# SAU-G0-EX_microSD.net
KiCad netlist of a schematic drawn in Altium Designer
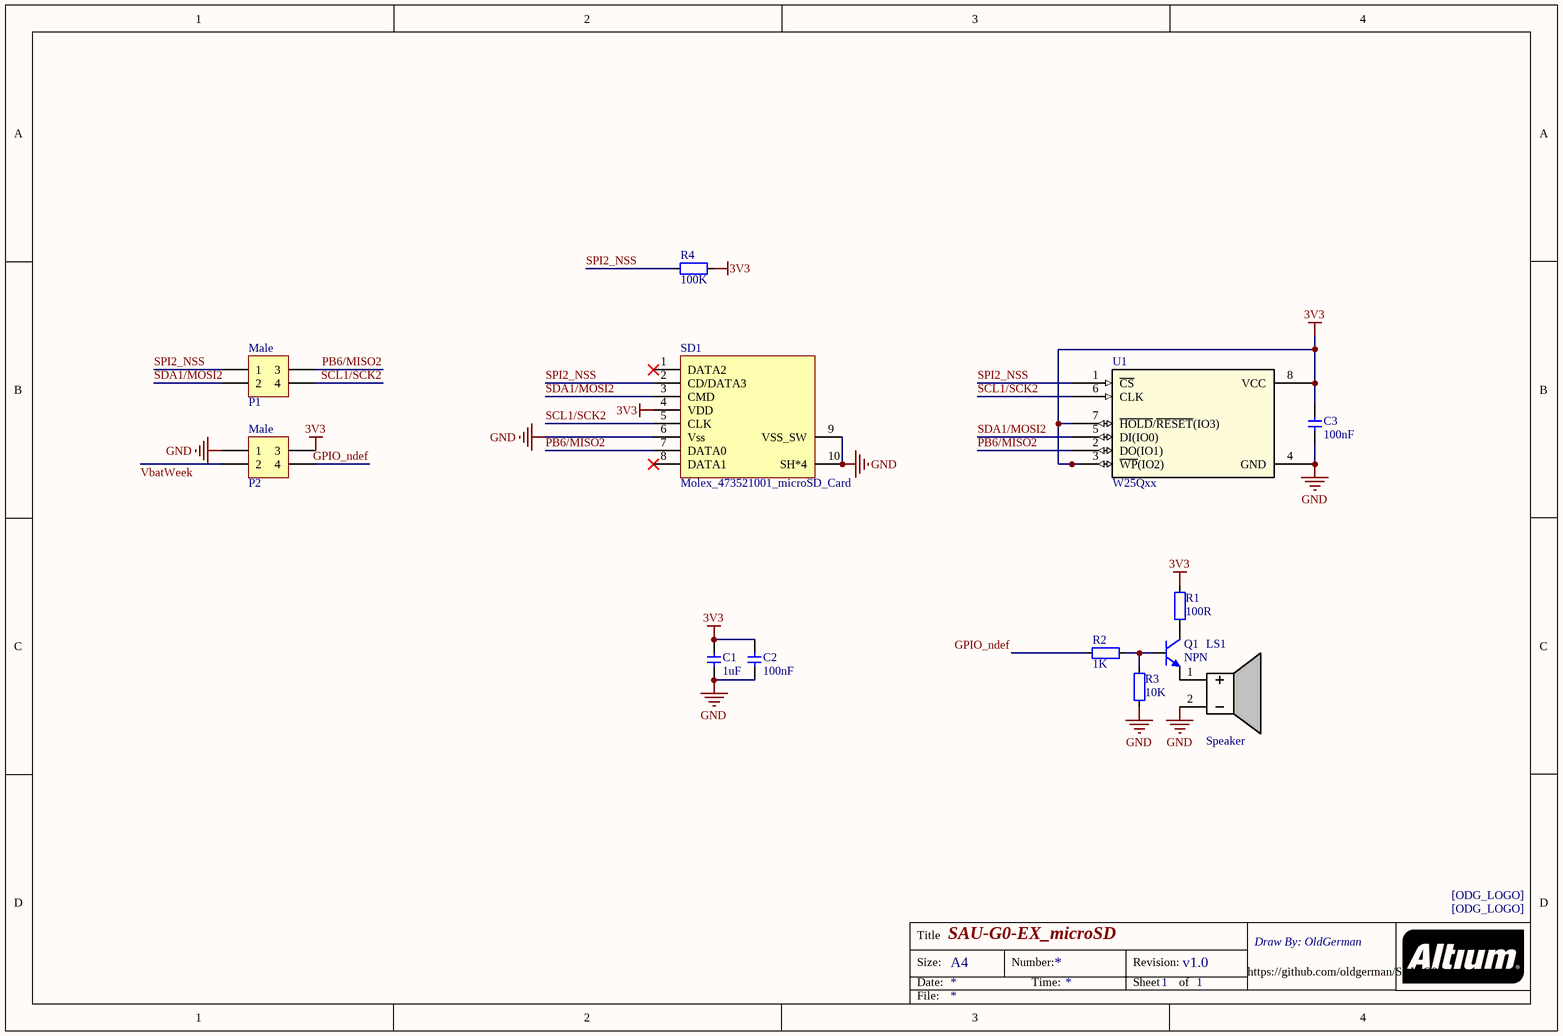
[diagram p0: SAU-G0-EX_microSD.SchDoc]

(export (version "E")
  (design (tool "Eeschema 10.0.6"))
  (components
    (comp (ref "C1")
      (value "1uF")
      (footprint "C0402")
      (description "Capacitor")
      (libsource (lib "ODG_AD_Lib") (part "CAP"))
    )
    (comp (ref "C2")
      (value "100nF")
      (footprint "C0402")
      (description "Capacitor")
      (libsource (lib "ODG_AD_Lib") (part "CAP"))
    )
    (comp (ref "C3")
      (value "100nF")
      (footprint "C0402")
      (description "Capacitor")
      (libsource (lib "ODG_AD_Lib") (part "CAP"))
    )
    (comp (ref "LS1")
      (value "Speaker")
      (footprint "压电陶瓷蜂鸣片12MM")
      (description "蜂鸣器")
      (libsource (lib "ODG_AD_Lib") (part "Speaker"))
    )
    (comp (ref "ODG1")
      (value "ODG_LOGO")
      (footprint "ODG_LOGO_soldermask")
      (libsource (lib "ODG_AD_Lib") (part "ODG_LOGO"))
    )
    (comp (ref "ODG2")
      (value "ODG_LOGO")
      (footprint "ODG_LOGO_soldermask")
      (libsource (lib "ODG_AD_Lib") (part "ODG_LOGO"))
    )
    (comp (ref "P1")
      (value "Male")
      (footprint "2.0mm_Male_2x2")
      (libsource (lib "ODG_AD_Lib") (part "CONN_2X2"))
    )
    (comp (ref "P2")
      (value "Male")
      (footprint "2.0mm_Male_2x2")
      (libsource (lib "ODG_AD_Lib") (part "CONN_2X2"))
    )
    (comp (ref "Q1")
      (value "NPN")
      (footprint "DIODES SOT-323-3")
      (description "NPN型")
      (fields (field (name "版权归属") "源创客"))
      (libsource (lib "ODG_AD_Lib") (part "NPN"))
    )
    (comp (ref "R1")
      (value "100R")
      (footprint "R0402")
      (description "Resistor")
      (libsource (lib "ODG_AD_Lib") (part "RES"))
    )
    (comp (ref "R2")
      (value "1K")
      (footprint "R0402")
      (description "Resistor")
      (libsource (lib "") (part "RES_1"))
    )
    (comp (ref "R3")
      (value "10K")
      (footprint "R0402")
      (description "Resistor")
      (libsource (lib "ODG_AD_Lib") (part "RES"))
    )
    (comp (ref "R4")
      (value "100K")
      (footprint "R0402")
      (description "Resistor")
      (libsource (lib "") (part "RES_1"))
    )
    (comp (ref "SD1")
      (value "Molex_473521001_microSD_Card")
      (footprint "molex_473521001_microSD_Card")
      (libsource (lib "ODG_AD_Lib") (part "Molex_473521001_microSD_Card"))
    )
    (comp (ref "U1")
      (value "W25Qxx")
      (footprint "WIN_SS-8_WIN-L")
      (description "No Description Available")
      (fields
        (field (name "MANUFACTURER_PART_NUMBER") "W25Q16DVSSIG")
        (field (name "COPYRIGHT") "Copyright (C) 2022 Ultra Librarian. All rights reserved.")
      )
      (libsource (lib "ODG_AD_Lib") (part "W25Qxx"))
    )
  )
  (nets
    (net (code "1") (name "/GPIO_ndef") (class "Default")
      (node (ref "P2") (pin "4") (pinfunction "4_4") (pintype "passive"))
      (node (ref "R2") (pin "1") (pinfunction "1_1") (pintype "passive"))
    )
    (net (code "2") (name "/PB6{slash}MISO2") (class "Default")
      (node (ref "P1") (pin "3") (pinfunction "3_3") (pintype "passive"))
      (node (ref "SD1") (pin "7") (pinfunction "DATA0_7") (pintype "passive"))
      (node (ref "U1") (pin "2") (pinfunction "DO(IO1)_2") (pintype "bidirectional"))
    )
    (net (code "3") (name "/SCL1{slash}SCK2") (class "Default")
      (node (ref "P1") (pin "4") (pinfunction "4_4") (pintype "passive"))
      (node (ref "SD1") (pin "5") (pinfunction "CLK_5") (pintype "passive"))
      (node (ref "U1") (pin "6") (pinfunction "CLK_6") (pintype "input"))
    )
    (net (code "4") (name "/SDA1{slash}MOSI2") (class "Default")
      (node (ref "P1") (pin "2") (pinfunction "2_2") (pintype "passive"))
      (node (ref "SD1") (pin "3") (pinfunction "CMD_3") (pintype "passive"))
      (node (ref "U1") (pin "5") (pinfunction "DI(IO0)_5") (pintype "bidirectional"))
    )
    (net (code "5") (name "/SPI2_NSS") (class "Default")
      (node (ref "P1") (pin "1") (pinfunction "1_1") (pintype "passive"))
      (node (ref "R4") (pin "1") (pinfunction "1_1") (pintype "passive"))
      (node (ref "SD1") (pin "2") (pinfunction "CD/DATA3_2") (pintype "passive"))
      (node (ref "U1") (pin "1") (pinfunction "~{CS}_1") (pintype "input"))
    )
    (net (code "6") (name "/VbatWeek") (class "Default")
      (node (ref "P2") (pin "2") (pinfunction "2_2") (pintype "passive"))
    )
    (net (code "7") (name "3V3") (class "Default")
      (node (ref "C1") (pin "2") (pinfunction "2_2") (pintype "passive"))
      (node (ref "C2") (pin "2") (pinfunction "2_2") (pintype "passive"))
      (node (ref "C3") (pin "1") (pinfunction "1_1") (pintype "passive"))
      (node (ref "P2") (pin "3") (pinfunction "3_3") (pintype "passive"))
      (node (ref "R1") (pin "2") (pinfunction "2_2") (pintype "passive"))
      (node (ref "R4") (pin "2") (pinfunction "2_2") (pintype "passive"))
      (node (ref "SD1") (pin "4") (pinfunction "VDD_4") (pintype "passive"))
      (node (ref "U1") (pin "3") (pinfunction "~{WP}(IO2)_3") (pintype "bidirectional"))
      (node (ref "U1") (pin "7") (pinfunction "~{HOLD}/~{RESET}(IO3)_7") (pintype "bidirectional"))
      (node (ref "U1") (pin "8") (pinfunction "VCC_8") (pintype "power_in"))
    )
    (net (code "8") (name "GND") (class "Default")
      (node (ref "C1") (pin "1") (pinfunction "1_1") (pintype "passive"))
      (node (ref "C2") (pin "1") (pinfunction "1_1") (pintype "passive"))
      (node (ref "C3") (pin "2") (pinfunction "2_2") (pintype "passive"))
      (node (ref "LS1") (pin "2") (pinfunction "-_2") (pintype "passive"))
      (node (ref "P2") (pin "1") (pinfunction "1_1") (pintype "passive"))
      (node (ref "R3") (pin "1") (pinfunction "1_1") (pintype "passive"))
      (node (ref "SD1") (pin "10") (pinfunction "SH*4_10") (pintype "passive"))
      (node (ref "SD1") (pin "6") (pinfunction "Vss_6") (pintype "passive"))
      (node (ref "SD1") (pin "9") (pinfunction "VSS_SW_9") (pintype "passive"))
      (node (ref "U1") (pin "4") (pinfunction "GND_4") (pintype "power_in"))
    )
    (net (code "9") (name "Net-(LS1-+)") (class "Default")
      (node (ref "LS1") (pin "1") (pinfunction "+_1") (pintype "passive"))
      (node (ref "Q1") (pin "2") (pinfunction "E_2") (pintype "passive"))
    )
    (net (code "10") (name "Net-(Q1-B)") (class "Default")
      (node (ref "Q1") (pin "1") (pinfunction "B_1") (pintype "passive"))
      (node (ref "R2") (pin "2") (pinfunction "2_2") (pintype "passive"))
      (node (ref "R3") (pin "2") (pinfunction "2_2") (pintype "passive"))
    )
    (net (code "11") (name "Net-(Q1-C)") (class "Default")
      (node (ref "Q1") (pin "3") (pinfunction "C_3") (pintype "passive"))
      (node (ref "R1") (pin "1") (pinfunction "1_1") (pintype "passive"))
    )
    (net (code "12") (name "unconnected-(SD1-DATA1-Pad8)") (class "Default")
      (node (ref "SD1") (pin "8") (pinfunction "DATA1_8") (pintype "passive+no_connect"))
    )
    (net (code "13") (name "unconnected-(SD1-DATA2-Pad1)") (class "Default")
      (node (ref "SD1") (pin "1") (pinfunction "DATA2_1") (pintype "passive+no_connect"))
    )
  )
)
